# ESP8266.net
KiCad netlist of a schematic drawn in Altium Designer
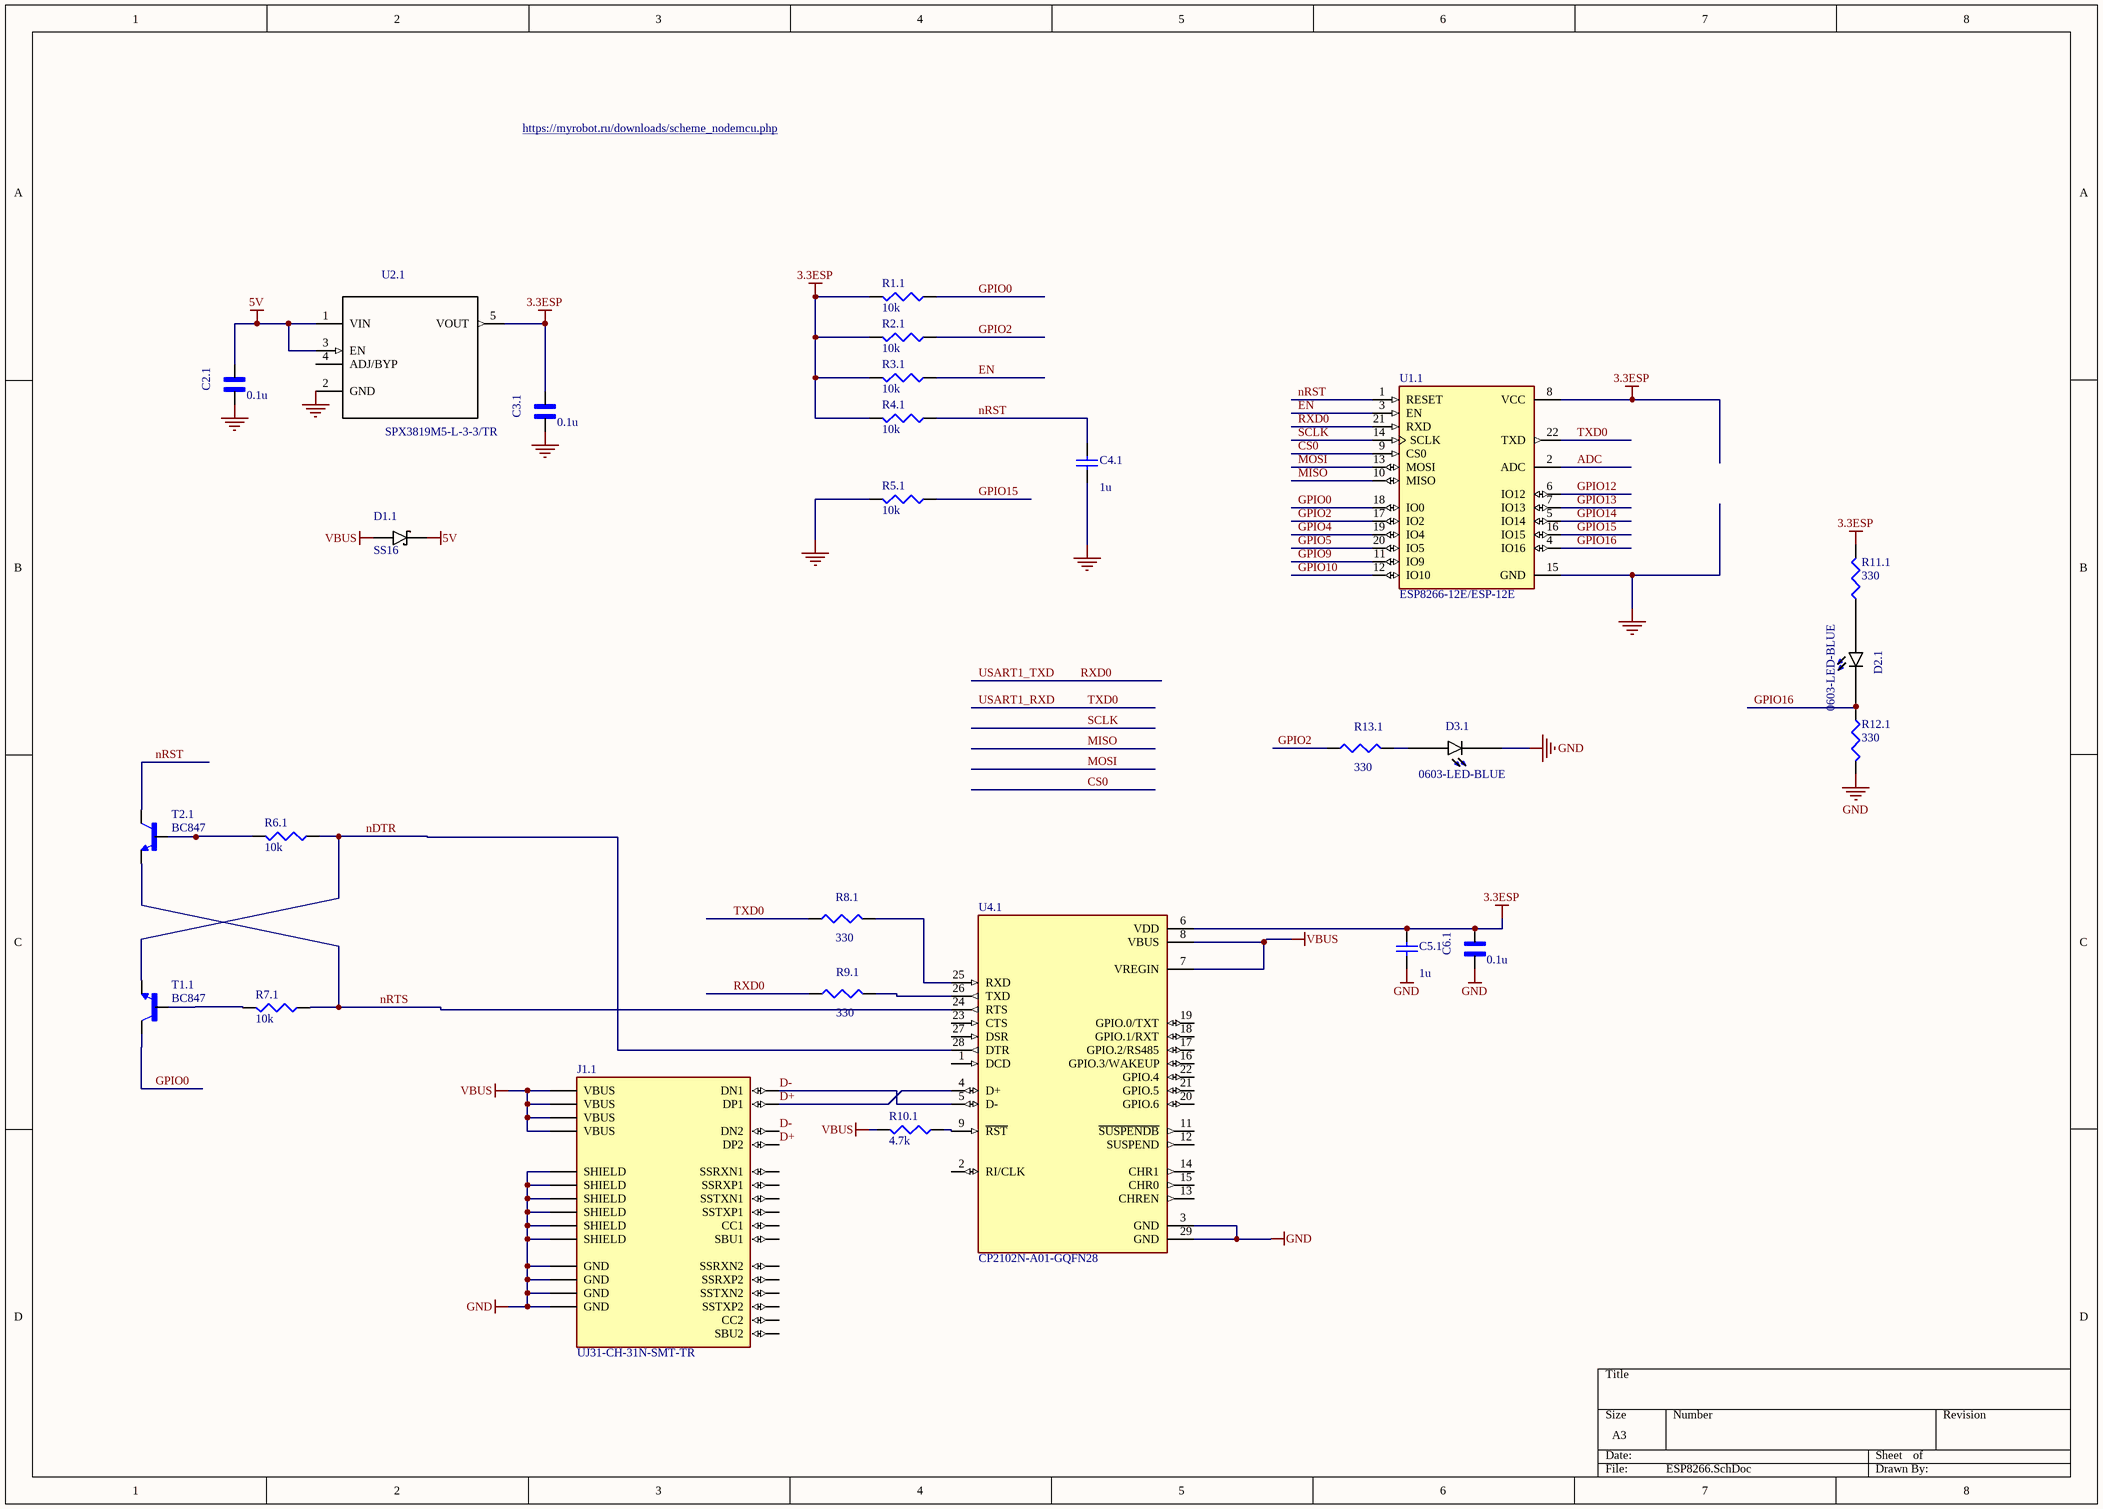
[diagram p0: ESP8266.SchDoc]

(export (version "E")
  (design (tool "Eeschema 10.0.6"))
  (components
    (comp (ref "C2.1")
      (value "0.1u")
      (footprint "*CAPC1608X90")
      (description "Cap Thin Film 0.1uf 50v 0603")
      (fields (field (name "MF") "AVX") (field (name "MP") "GX035C104MAT2-500"))
      (libsource (lib "lib") (part "GX035C104MAT2-500"))
    )
    (comp (ref "C3.1")
      (value "0.1u")
      (footprint "*CAPC1608X90")
      (description "Cap Thin Film 0.1uf 50v 0603")
      (fields (field (name "MF") "AVX") (field (name "MP") "GX035C104MAT2-500"))
      (libsource (lib "lib") (part "GX035C104MAT2-500"))
    )
    (comp (ref "C4.1")
      (value "1u")
      (footprint "1608[0603]")
      (description "Capacitor (Semiconductor SIM Model)")
      (fields (field (name "Comment") "Cap Semi") (field (name "PUBLISHER") "Altium Limited"))
      (libsource (lib "Miscellaneous Devices") (part "Cap Semi"))
    )
    (comp (ref "C5.1")
      (value "1u")
      (footprint "1608[0603]")
      (description "Capacitor (Semiconductor SIM Model)")
      (fields (field (name "Comment") "Cap Semi") (field (name "PUBLISHER") "Altium Limited"))
      (libsource (lib "Miscellaneous Devices") (part "Cap Semi"))
    )
    (comp (ref "C6.1")
      (value "0.1u")
      (footprint "*CAPC1608X90")
      (description "Cap Thin Film 0.1uf 50v 0603")
      (fields (field (name "MF") "AVX") (field (name "MP") "GX035C104MAT2-500 or CL10B104JB8NNNC"))
      (libsource (lib "lib") (part "GX035C104MAT2-500"))
    )
    (comp (ref "D1.1")
      (value "SS16")
      (footprint "*DIOM5227X250N_SS16(Primary)")
      (description "Diode Schottky 60V 1A Surface Mount SMA")
      (libsource (lib "lib") (part "SS16"))
    )
    (comp (ref "D2.1")
      (value "0603-LED-BLUE")
      (footprint "*LEDM1608X80_LTE-C1906R-14(Primary)")
      (description "LED IrLED Chip LED 2-Pin SMD T/R")
      (libsource (lib "lib") (part "LTE-C1906R-14"))
    )
    (comp (ref "D3.1")
      (value "0603-LED-BLUE")
      (footprint "*LEDM1608X80_LTE-C1906R-14(Primary)")
      (description "LED IrLED Chip LED 2-Pin SMD T/R")
      (libsource (lib "lib") (part "LTE-C1906R-14"))
    )
    (comp (ref "J1.1")
      (value "UJ31-CH-31N-SMT-TR")
      (footprint "CUI_UJ31-CH-31N-SMT-TR")
      (description "Type C, USB 3.1 Gen 2, 5 A, Right Angle, Surface Mount _SMT_, USB Receptacle")
      (fields (field (name "MF") "CUI Devices"))
      (libsource (lib "lib") (part "UJ31-CH-31N-SMT-TR"))
    )
    (comp (ref "R1.1")
      (value "10k")
      (footprint "J1-0603")
      (description "Resistor")
      (fields (field (name "MP") "10K 1% 0603") (field (name "Comment") "Res3"))
      (libsource (lib "Miscellaneous Devices") (part "Res3"))
    )
    (comp (ref "R2.1")
      (value "10k")
      (footprint "J1-0603")
      (description "Resistor")
      (fields (field (name "MP") "10K 1% 0603") (field (name "Comment") "Res3"))
      (libsource (lib "Miscellaneous Devices") (part "Res3"))
    )
    (comp (ref "R3.1")
      (value "10k")
      (footprint "J1-0603")
      (description "Resistor")
      (fields (field (name "MP") "10K 1% 0603") (field (name "Comment") "Res3"))
      (libsource (lib "Miscellaneous Devices") (part "Res3"))
    )
    (comp (ref "R4.1")
      (value "10k")
      (footprint "J1-0603")
      (description "Resistor")
      (fields (field (name "MP") "10K 1% 0603") (field (name "Comment") "Res3"))
      (libsource (lib "Miscellaneous Devices") (part "Res3"))
    )
    (comp (ref "R5.1")
      (value "10k")
      (footprint "J1-0603")
      (description "Resistor")
      (fields (field (name "MP") "10K 1% 0603") (field (name "Comment") "Res3"))
      (libsource (lib "Miscellaneous Devices") (part "Res3"))
    )
    (comp (ref "R6.1")
      (value "10k")
      (footprint "J1-0603")
      (description "Resistor")
      (fields (field (name "MP") "10K 1% 0603") (field (name "Comment") "Res3"))
      (libsource (lib "Miscellaneous Devices") (part "Res3"))
    )
    (comp (ref "R7.1")
      (value "10k")
      (footprint "J1-0603")
      (description "Resistor")
      (fields (field (name "MP") "10K 1% 0603") (field (name "Comment") "Res3"))
      (libsource (lib "Miscellaneous Devices") (part "Res3"))
    )
    (comp (ref "R8.1")
      (value "330")
      (footprint "J1-0603")
      (description "Resistor")
      (fields (field (name "MP") "RC0603FR-07330RL") (field (name "Comment") "Res3"))
      (libsource (lib "Miscellaneous Devices") (part "Res3"))
    )
    (comp (ref "R9.1")
      (value "330")
      (footprint "J1-0603")
      (description "Resistor")
      (fields (field (name "MP") "RC0603FR-07330RL") (field (name "Comment") "Res3"))
      (libsource (lib "Miscellaneous Devices") (part "Res3"))
    )
    (comp (ref "R10.1")
      (value "4.7k")
      (footprint "J1-0603")
      (description "Resistor")
      (fields (field (name "MP") "4.7K 1% 0603") (field (name "Comment") "Res3"))
      (libsource (lib "Miscellaneous Devices") (part "Res3"))
    )
    (comp (ref "R11.1")
      (value "330")
      (footprint "J1-0603")
      (description "Resistor")
      (fields (field (name "MP") "RC0603FR-07330RL") (field (name "Comment") "Res3"))
      (libsource (lib "Miscellaneous Devices") (part "Res3"))
    )
    (comp (ref "R12.1")
      (value "330")
      (footprint "J1-0603")
      (description "Resistor")
      (fields (field (name "MP") "RC0603FR-07330RL") (field (name "Comment") "Res3"))
      (libsource (lib "Miscellaneous Devices") (part "Res3"))
    )
    (comp (ref "R13.1")
      (value "330")
      (footprint "J1-0603")
      (description "Resistor")
      (fields (field (name "MP") "RC0603FR-07330RL") (field (name "Comment") "Res3"))
      (libsource (lib "Miscellaneous Devices") (part "Res3"))
    )
    (comp (ref "T1.1")
      (value "BC847")
      (footprint "SOT23")
      (description "<b>NPN TRANSISTOR</b>")
      (fields (field (name "MF") "{'manufacturer': u'Rectron'}"))
      (libsource (lib "SnapEDA_Library") (part "BC847"))
    )
    (comp (ref "T2.1")
      (value "BC847")
      (footprint "SOT23")
      (description "<b>NPN TRANSISTOR</b>")
      (fields (field (name "MF") "{'manufacturer': u'Rectron'}"))
      (libsource (lib "") (part "BC847_1"))
    )
    (comp (ref "U1.1")
      (value "ESP8266-12E/ESP-12E")
      (footprint "XCVR_ESP8266-12E/ESP-12E")
      (description "ESP-12E WiFi Module")
      (fields (field (name "MF") "{'manufacturer': u'AI-Thinker'}"))
      (libsource (lib "SnapEDA_Library") (part "ESP8266-12E/ESP-12E"))
    )
    (comp (ref "U2.1")
      (value "SPX3819M5-L-3-3/TR")
      (footprint "*SOT95P280X145-5N")
      (description "Low Dropout Voltage Regulator, Adjustable 0.5A, В±1%, 2.5 to 16 Vin, 5-Pin SOT-23")
      (fields (field (name "MF") "MaxLinear, Inc."))
      (libsource (lib "DC_DC") (part "SPX3819M5-L"))
    )
    (comp (ref "U4.1")
      (value "CP2102N-A01-GQFN28")
      (footprint "QFN50P500X500X80-29N")
      (description "Ic Bridge Usb To Uart 28qfn")
      (fields (field (name "MF") "{'manufacturer': u'Silicon Labs'}"))
      (libsource (lib "SnapEDA_Library") (part "CP2102N-A01-GQFN28"))
    )
  )
  (nets
    (net (code "1") (name "/ADC") (class "Default")
      (node (ref "U1.1") (pin "2") (pinfunction "ADC_2") (pintype "passive"))
    )
    (net (code "2") (name "/CS0") (class "Default")
      (node (ref "U1.1") (pin "9") (pinfunction "CS0_9") (pintype "input"))
    )
    (net (code "3") (name "/D+") (class "Default")
      (node (ref "J1.1") (pin "A6") (pinfunction "DP1_A6") (pintype "bidirectional"))
      (node (ref "J1.1") (pin "B6") (pinfunction "DP2_B6") (pintype "bidirectional"))
      (node (ref "U4.1") (pin "4") (pinfunction "D+_4") (pintype "bidirectional"))
    )
    (net (code "4") (name "/D-") (class "Default")
      (node (ref "J1.1") (pin "A7") (pinfunction "DN1_A7") (pintype "bidirectional"))
      (node (ref "J1.1") (pin "B7") (pinfunction "DN2_B7") (pintype "bidirectional"))
      (node (ref "U4.1") (pin "5") (pinfunction "D-_5") (pintype "bidirectional"))
    )
    (net (code "5") (name "/EN") (class "Default")
      (node (ref "R3.1") (pin "1") (pinfunction "1_1") (pintype "passive"))
      (node (ref "U1.1") (pin "3") (pinfunction "EN_3") (pintype "input"))
    )
    (net (code "6") (name "/GPIO0") (class "Default")
      (node (ref "R1.1") (pin "1") (pinfunction "1_1") (pintype "passive"))
      (node (ref "T1.1") (pin "3") (pinfunction "C_3") (pintype "passive"))
      (node (ref "U1.1") (pin "18") (pinfunction "IO0_18") (pintype "bidirectional"))
    )
    (net (code "7") (name "/GPIO2") (class "Default")
      (node (ref "R13.1") (pin "1") (pinfunction "1_1") (pintype "passive"))
      (node (ref "R2.1") (pin "1") (pinfunction "1_1") (pintype "passive"))
      (node (ref "U1.1") (pin "17") (pinfunction "IO2_17") (pintype "bidirectional"))
    )
    (net (code "8") (name "/GPIO4") (class "Default")
      (node (ref "U1.1") (pin "19") (pinfunction "IO4_19") (pintype "bidirectional"))
    )
    (net (code "9") (name "/GPIO5") (class "Default")
      (node (ref "U1.1") (pin "20") (pinfunction "IO5_20") (pintype "bidirectional"))
    )
    (net (code "10") (name "/GPIO9") (class "Default")
      (node (ref "U1.1") (pin "11") (pinfunction "IO9_11") (pintype "bidirectional"))
    )
    (net (code "11") (name "/GPIO10") (class "Default")
      (node (ref "U1.1") (pin "12") (pinfunction "IO10_12") (pintype "bidirectional"))
    )
    (net (code "12") (name "/GPIO12") (class "Default")
      (node (ref "U1.1") (pin "6") (pinfunction "IO12_6") (pintype "bidirectional"))
    )
    (net (code "13") (name "/GPIO13") (class "Default")
      (node (ref "U1.1") (pin "7") (pinfunction "IO13_7") (pintype "bidirectional"))
    )
    (net (code "14") (name "/GPIO14") (class "Default")
      (node (ref "U1.1") (pin "5") (pinfunction "IO14_5") (pintype "bidirectional"))
    )
    (net (code "15") (name "/GPIO15") (class "Default")
      (node (ref "R5.1") (pin "1") (pinfunction "1_1") (pintype "passive"))
      (node (ref "U1.1") (pin "16") (pinfunction "IO15_16") (pintype "bidirectional"))
    )
    (net (code "16") (name "/GPIO16") (class "Default")
      (node (ref "D2.1") (pin "C") (pinfunction "C_C") (pintype "passive"))
      (node (ref "R12.1") (pin "1") (pinfunction "1_1") (pintype "passive"))
      (node (ref "U1.1") (pin "4") (pinfunction "IO16_4") (pintype "bidirectional"))
    )
    (net (code "17") (name "/MISO") (class "Default")
      (node (ref "U1.1") (pin "10") (pinfunction "MISO_10") (pintype "bidirectional"))
    )
    (net (code "18") (name "/MOSI") (class "Default")
      (node (ref "U1.1") (pin "13") (pinfunction "MOSI_13") (pintype "bidirectional"))
    )
    (net (code "19") (name "/RXD0") (class "Default")
      (node (ref "R9.1") (pin "1") (pinfunction "1_1") (pintype "passive"))
      (node (ref "U1.1") (pin "21") (pinfunction "RXD_21") (pintype "input"))
    )
    (net (code "20") (name "/SCLK") (class "Default")
      (node (ref "U1.1") (pin "14") (pinfunction "SCLK_14") (pintype "input"))
    )
    (net (code "21") (name "/TXD0") (class "Default")
      (node (ref "R8.1") (pin "1") (pinfunction "1_1") (pintype "passive"))
      (node (ref "U1.1") (pin "22") (pinfunction "TXD_22") (pintype "output"))
    )
    (net (code "22") (name "/nDTR") (class "Default")
      (node (ref "R6.1") (pin "1") (pinfunction "1_1") (pintype "passive"))
      (node (ref "T1.1") (pin "2") (pinfunction "E_2") (pintype "passive"))
      (node (ref "U4.1") (pin "28") (pinfunction "DTR_28") (pintype "output"))
    )
    (net (code "23") (name "/nRST") (class "Default")
      (node (ref "C4.1") (pin "1") (pinfunction "1_1") (pintype "passive"))
      (node (ref "R4.1") (pin "1") (pinfunction "1_1") (pintype "passive"))
      (node (ref "T2.1") (pin "3") (pinfunction "C_3") (pintype "passive"))
      (node (ref "U1.1") (pin "1") (pinfunction "RESET_1") (pintype "input"))
    )
    (net (code "24") (name "/nRTS") (class "Default")
      (node (ref "R7.1") (pin "1") (pinfunction "1_1") (pintype "passive"))
      (node (ref "T2.1") (pin "2") (pinfunction "E_2") (pintype "passive"))
      (node (ref "U4.1") (pin "24") (pinfunction "RTS_24") (pintype "output"))
    )
    (net (code "25") (name "3.3ESP") (class "Default")
      (node (ref "C3.1") (pin "1") (pinfunction "1_1") (pintype "passive"))
      (node (ref "C5.1") (pin "1") (pinfunction "1_1") (pintype "passive"))
      (node (ref "C6.1") (pin "1") (pinfunction "1_1") (pintype "passive"))
      (node (ref "R1.1") (pin "2") (pinfunction "2_2") (pintype "passive"))
      (node (ref "R11.1") (pin "2") (pinfunction "2_2") (pintype "passive"))
      (node (ref "R2.1") (pin "2") (pinfunction "2_2") (pintype "passive"))
      (node (ref "R3.1") (pin "2") (pinfunction "2_2") (pintype "passive"))
      (node (ref "R4.1") (pin "2") (pinfunction "2_2") (pintype "passive"))
      (node (ref "U1.1") (pin "8") (pinfunction "VCC_8") (pintype "power_in"))
      (node (ref "U2.1") (pin "5") (pinfunction "VOUT_5") (pintype "output"))
      (node (ref "U4.1") (pin "6") (pinfunction "VDD_6") (pintype "power_in"))
    )
    (net (code "26") (name "5V") (class "Default")
      (node (ref "C2.1") (pin "1") (pinfunction "1_1") (pintype "passive"))
      (node (ref "D1.1") (pin "C") (pinfunction "K_C") (pintype "passive"))
      (node (ref "U2.1") (pin "1") (pinfunction "VIN_1") (pintype "power_in"))
      (node (ref "U2.1") (pin "3") (pinfunction "EN_3") (pintype "input"))
    )
    (net (code "27") (name "GND") (class "Default")
      (node (ref "C2.1") (pin "2") (pinfunction "2_2") (pintype "passive"))
      (node (ref "C3.1") (pin "2") (pinfunction "2_2") (pintype "passive"))
      (node (ref "C4.1") (pin "2") (pinfunction "2_2") (pintype "passive"))
      (node (ref "C5.1") (pin "2") (pinfunction "2_2") (pintype "passive"))
      (node (ref "C6.1") (pin "2") (pinfunction "2_2") (pintype "passive"))
      (node (ref "D3.1") (pin "C") (pinfunction "C_C") (pintype "passive"))
      (node (ref "J1.1") (pin "A1") (pinfunction "GND_A1") (pintype "power_in"))
      (node (ref "J1.1") (pin "A12") (pinfunction "GND_A12") (pintype "power_in"))
      (node (ref "J1.1") (pin "B1") (pinfunction "GND_B1") (pintype "power_in"))
      (node (ref "J1.1") (pin "B12") (pinfunction "GND_B12") (pintype "power_in"))
      (node (ref "J1.1") (pin "SH1") (pinfunction "SHIELD_SH1") (pintype "power_in"))
      (node (ref "J1.1") (pin "SH2") (pinfunction "SHIELD_SH2") (pintype "power_in"))
      (node (ref "J1.1") (pin "SH3") (pinfunction "SHIELD_SH3") (pintype "power_in"))
      (node (ref "J1.1") (pin "SH4") (pinfunction "SHIELD_SH4") (pintype "power_in"))
      (node (ref "J1.1") (pin "SH5") (pinfunction "SHIELD_SH5") (pintype "power_in"))
      (node (ref "J1.1") (pin "SH6") (pinfunction "SHIELD_SH6") (pintype "power_in"))
      (node (ref "R12.1") (pin "2") (pinfunction "2_2") (pintype "passive"))
      (node (ref "R5.1") (pin "2") (pinfunction "2_2") (pintype "passive"))
      (node (ref "U1.1") (pin "15") (pinfunction "GND_15") (pintype "power_in"))
      (node (ref "U2.1") (pin "2") (pinfunction "GND_2") (pintype "passive"))
      (node (ref "U4.1") (pin "29") (pinfunction "GND_29") (pintype "power_in"))
      (node (ref "U4.1") (pin "3") (pinfunction "GND_3") (pintype "power_in"))
    )
    (net (code "28") (name "Net-(D2.1-PadA)") (class "Default")
      (node (ref "D2.1") (pin "A") (pinfunction "A_A") (pintype "passive"))
      (node (ref "R11.1") (pin "1") (pinfunction "1_1") (pintype "passive"))
    )
    (net (code "29") (name "Net-(D3.1-PadA)") (class "Default")
      (node (ref "D3.1") (pin "A") (pinfunction "A_A") (pintype "passive"))
      (node (ref "R13.1") (pin "2") (pinfunction "2_2") (pintype "passive"))
    )
    (net (code "30") (name "Net-(T1.1-B)") (class "Default")
      (node (ref "R7.1") (pin "2") (pinfunction "2_2") (pintype "passive"))
      (node (ref "T1.1") (pin "1") (pinfunction "B_1") (pintype "passive"))
    )
    (net (code "31") (name "Net-(T2.1-B)") (class "Default")
      (node (ref "R6.1") (pin "2") (pinfunction "2_2") (pintype "passive"))
      (node (ref "T2.1") (pin "1") (pinfunction "B_1") (pintype "passive"))
    )
    (net (code "32") (name "Net-(U4.1-RXD)") (class "Default")
      (node (ref "R8.1") (pin "2") (pinfunction "2_2") (pintype "passive"))
      (node (ref "U4.1") (pin "25") (pinfunction "RXD_25") (pintype "input"))
    )
    (net (code "33") (name "Net-(U4.1-TXD)") (class "Default")
      (node (ref "R9.1") (pin "2") (pinfunction "2_2") (pintype "passive"))
      (node (ref "U4.1") (pin "26") (pinfunction "TXD_26") (pintype "output"))
    )
    (net (code "34") (name "Net-(U4.1-~{RST})") (class "Default")
      (node (ref "R10.1") (pin "1") (pinfunction "1_1") (pintype "passive"))
      (node (ref "U4.1") (pin "9") (pinfunction "~{RST}_9") (pintype "input"))
    )
    (net (code "35") (name "VBUS") (class "Default")
      (node (ref "D1.1") (pin "A") (pinfunction "A_A") (pintype "passive"))
      (node (ref "J1.1") (pin "A4") (pinfunction "VBUS_A4") (pintype "power_in"))
      (node (ref "J1.1") (pin "A9") (pinfunction "VBUS_A9") (pintype "power_in"))
      (node (ref "J1.1") (pin "B4") (pinfunction "VBUS_B4") (pintype "power_in"))
      (node (ref "J1.1") (pin "B9") (pinfunction "VBUS_B9") (pintype "power_in"))
      (node (ref "R10.1") (pin "2") (pinfunction "2_2") (pintype "passive"))
      (node (ref "U4.1") (pin "7") (pinfunction "VREGIN_7") (pintype "power_in"))
      (node (ref "U4.1") (pin "8") (pinfunction "VBUS_8") (pintype "power_in"))
    )
    (net (code "36") (name "unconnected-(J1.1-CC1-PadA5)") (class "Default")
      (node (ref "J1.1") (pin "A5") (pinfunction "CC1_A5") (pintype "bidirectional"))
    )
    (net (code "37") (name "unconnected-(J1.1-CC2-PadB5)") (class "Default")
      (node (ref "J1.1") (pin "B5") (pinfunction "CC2_B5") (pintype "bidirectional"))
    )
    (net (code "38") (name "unconnected-(J1.1-SBU1-PadA8)") (class "Default")
      (node (ref "J1.1") (pin "A8") (pinfunction "SBU1_A8") (pintype "bidirectional"))
    )
    (net (code "39") (name "unconnected-(J1.1-SBU2-PadB8)") (class "Default")
      (node (ref "J1.1") (pin "B8") (pinfunction "SBU2_B8") (pintype "bidirectional"))
    )
    (net (code "40") (name "unconnected-(J1.1-SSRXN1-PadB10)") (class "Default")
      (node (ref "J1.1") (pin "B10") (pinfunction "SSRXN1_B10") (pintype "bidirectional"))
    )
    (net (code "41") (name "unconnected-(J1.1-SSRXN2-PadA10)") (class "Default")
      (node (ref "J1.1") (pin "A10") (pinfunction "SSRXN2_A10") (pintype "bidirectional"))
    )
    (net (code "42") (name "unconnected-(J1.1-SSRXP1-PadB11)") (class "Default")
      (node (ref "J1.1") (pin "B11") (pinfunction "SSRXP1_B11") (pintype "bidirectional"))
    )
    (net (code "43") (name "unconnected-(J1.1-SSRXP2-PadA11)") (class "Default")
      (node (ref "J1.1") (pin "A11") (pinfunction "SSRXP2_A11") (pintype "bidirectional"))
    )
    (net (code "44") (name "unconnected-(J1.1-SSTXN1-PadA3)") (class "Default")
      (node (ref "J1.1") (pin "A3") (pinfunction "SSTXN1_A3") (pintype "bidirectional"))
    )
    (net (code "45") (name "unconnected-(J1.1-SSTXN2-PadB3)") (class "Default")
      (node (ref "J1.1") (pin "B3") (pinfunction "SSTXN2_B3") (pintype "bidirectional"))
    )
    (net (code "46") (name "unconnected-(J1.1-SSTXP1-PadA2)") (class "Default")
      (node (ref "J1.1") (pin "A2") (pinfunction "SSTXP1_A2") (pintype "bidirectional"))
    )
    (net (code "47") (name "unconnected-(J1.1-SSTXP2-PadB2)") (class "Default")
      (node (ref "J1.1") (pin "B2") (pinfunction "SSTXP2_B2") (pintype "bidirectional"))
    )
    (net (code "48") (name "unconnected-(U2.1-ADJ{slash}BYP-Pad4)") (class "Default")
      (node (ref "U2.1") (pin "4") (pinfunction "ADJ/BYP_4") (pintype "passive"))
    )
    (net (code "49") (name "unconnected-(U4.1-CHR0-Pad15)") (class "Default")
      (node (ref "U4.1") (pin "15") (pinfunction "CHR0_15") (pintype "output"))
    )
    (net (code "50") (name "unconnected-(U4.1-CHR1-Pad14)") (class "Default")
      (node (ref "U4.1") (pin "14") (pinfunction "CHR1_14") (pintype "output"))
    )
    (net (code "51") (name "unconnected-(U4.1-CHREN-Pad13)") (class "Default")
      (node (ref "U4.1") (pin "13") (pinfunction "CHREN_13") (pintype "output"))
    )
    (net (code "52") (name "unconnected-(U4.1-CTS-Pad23)") (class "Default")
      (node (ref "U4.1") (pin "23") (pinfunction "CTS_23") (pintype "input"))
    )
    (net (code "53") (name "unconnected-(U4.1-DCD-Pad1)") (class "Default")
      (node (ref "U4.1") (pin "1") (pinfunction "DCD_1") (pintype "input"))
    )
    (net (code "54") (name "unconnected-(U4.1-DSR-Pad27)") (class "Default")
      (node (ref "U4.1") (pin "27") (pinfunction "DSR_27") (pintype "input"))
    )
    (net (code "55") (name "unconnected-(U4.1-GPIO.0{slash}TXT-Pad19)") (class "Default")
      (node (ref "U4.1") (pin "19") (pinfunction "GPIO.0/TXT_19") (pintype "bidirectional"))
    )
    (net (code "56") (name "unconnected-(U4.1-GPIO.1{slash}RXT-Pad18)") (class "Default")
      (node (ref "U4.1") (pin "18") (pinfunction "GPIO.1/RXT_18") (pintype "bidirectional"))
    )
    (net (code "57") (name "unconnected-(U4.1-GPIO.2{slash}RS485-Pad17)") (class "Default")
      (node (ref "U4.1") (pin "17") (pinfunction "GPIO.2/RS485_17") (pintype "bidirectional"))
    )
    (net (code "58") (name "unconnected-(U4.1-GPIO.3{slash}WAKEUP-Pad16)") (class "Default")
      (node (ref "U4.1") (pin "16") (pinfunction "GPIO.3/WAKEUP_16") (pintype "bidirectional"))
    )
    (net (code "59") (name "unconnected-(U4.1-GPIO.4-Pad22)") (class "Default")
      (node (ref "U4.1") (pin "22") (pinfunction "GPIO.4_22") (pintype "bidirectional"))
    )
    (net (code "60") (name "unconnected-(U4.1-GPIO.5-Pad21)") (class "Default")
      (node (ref "U4.1") (pin "21") (pinfunction "GPIO.5_21") (pintype "bidirectional"))
    )
    (net (code "61") (name "unconnected-(U4.1-GPIO.6-Pad20)") (class "Default")
      (node (ref "U4.1") (pin "20") (pinfunction "GPIO.6_20") (pintype "bidirectional"))
    )
    (net (code "62") (name "unconnected-(U4.1-RI{slash}CLK-Pad2)") (class "Default")
      (node (ref "U4.1") (pin "2") (pinfunction "RI/CLK_2") (pintype "bidirectional"))
    )
    (net (code "63") (name "unconnected-(U4.1-SUSPEND-Pad12)") (class "Default")
      (node (ref "U4.1") (pin "12") (pinfunction "SUSPEND_12") (pintype "output"))
    )
    (net (code "64") (name "unconnected-(U4.1-~{SUSPENDB}-Pad11)") (class "Default")
      (node (ref "U4.1") (pin "11") (pinfunction "~{SUSPENDB}_11") (pintype "output"))
    )
  )
)
